# SCH_DA2_fix_2023-07-17.net
KiCad netlist of a schematic drawn in EasyEDA
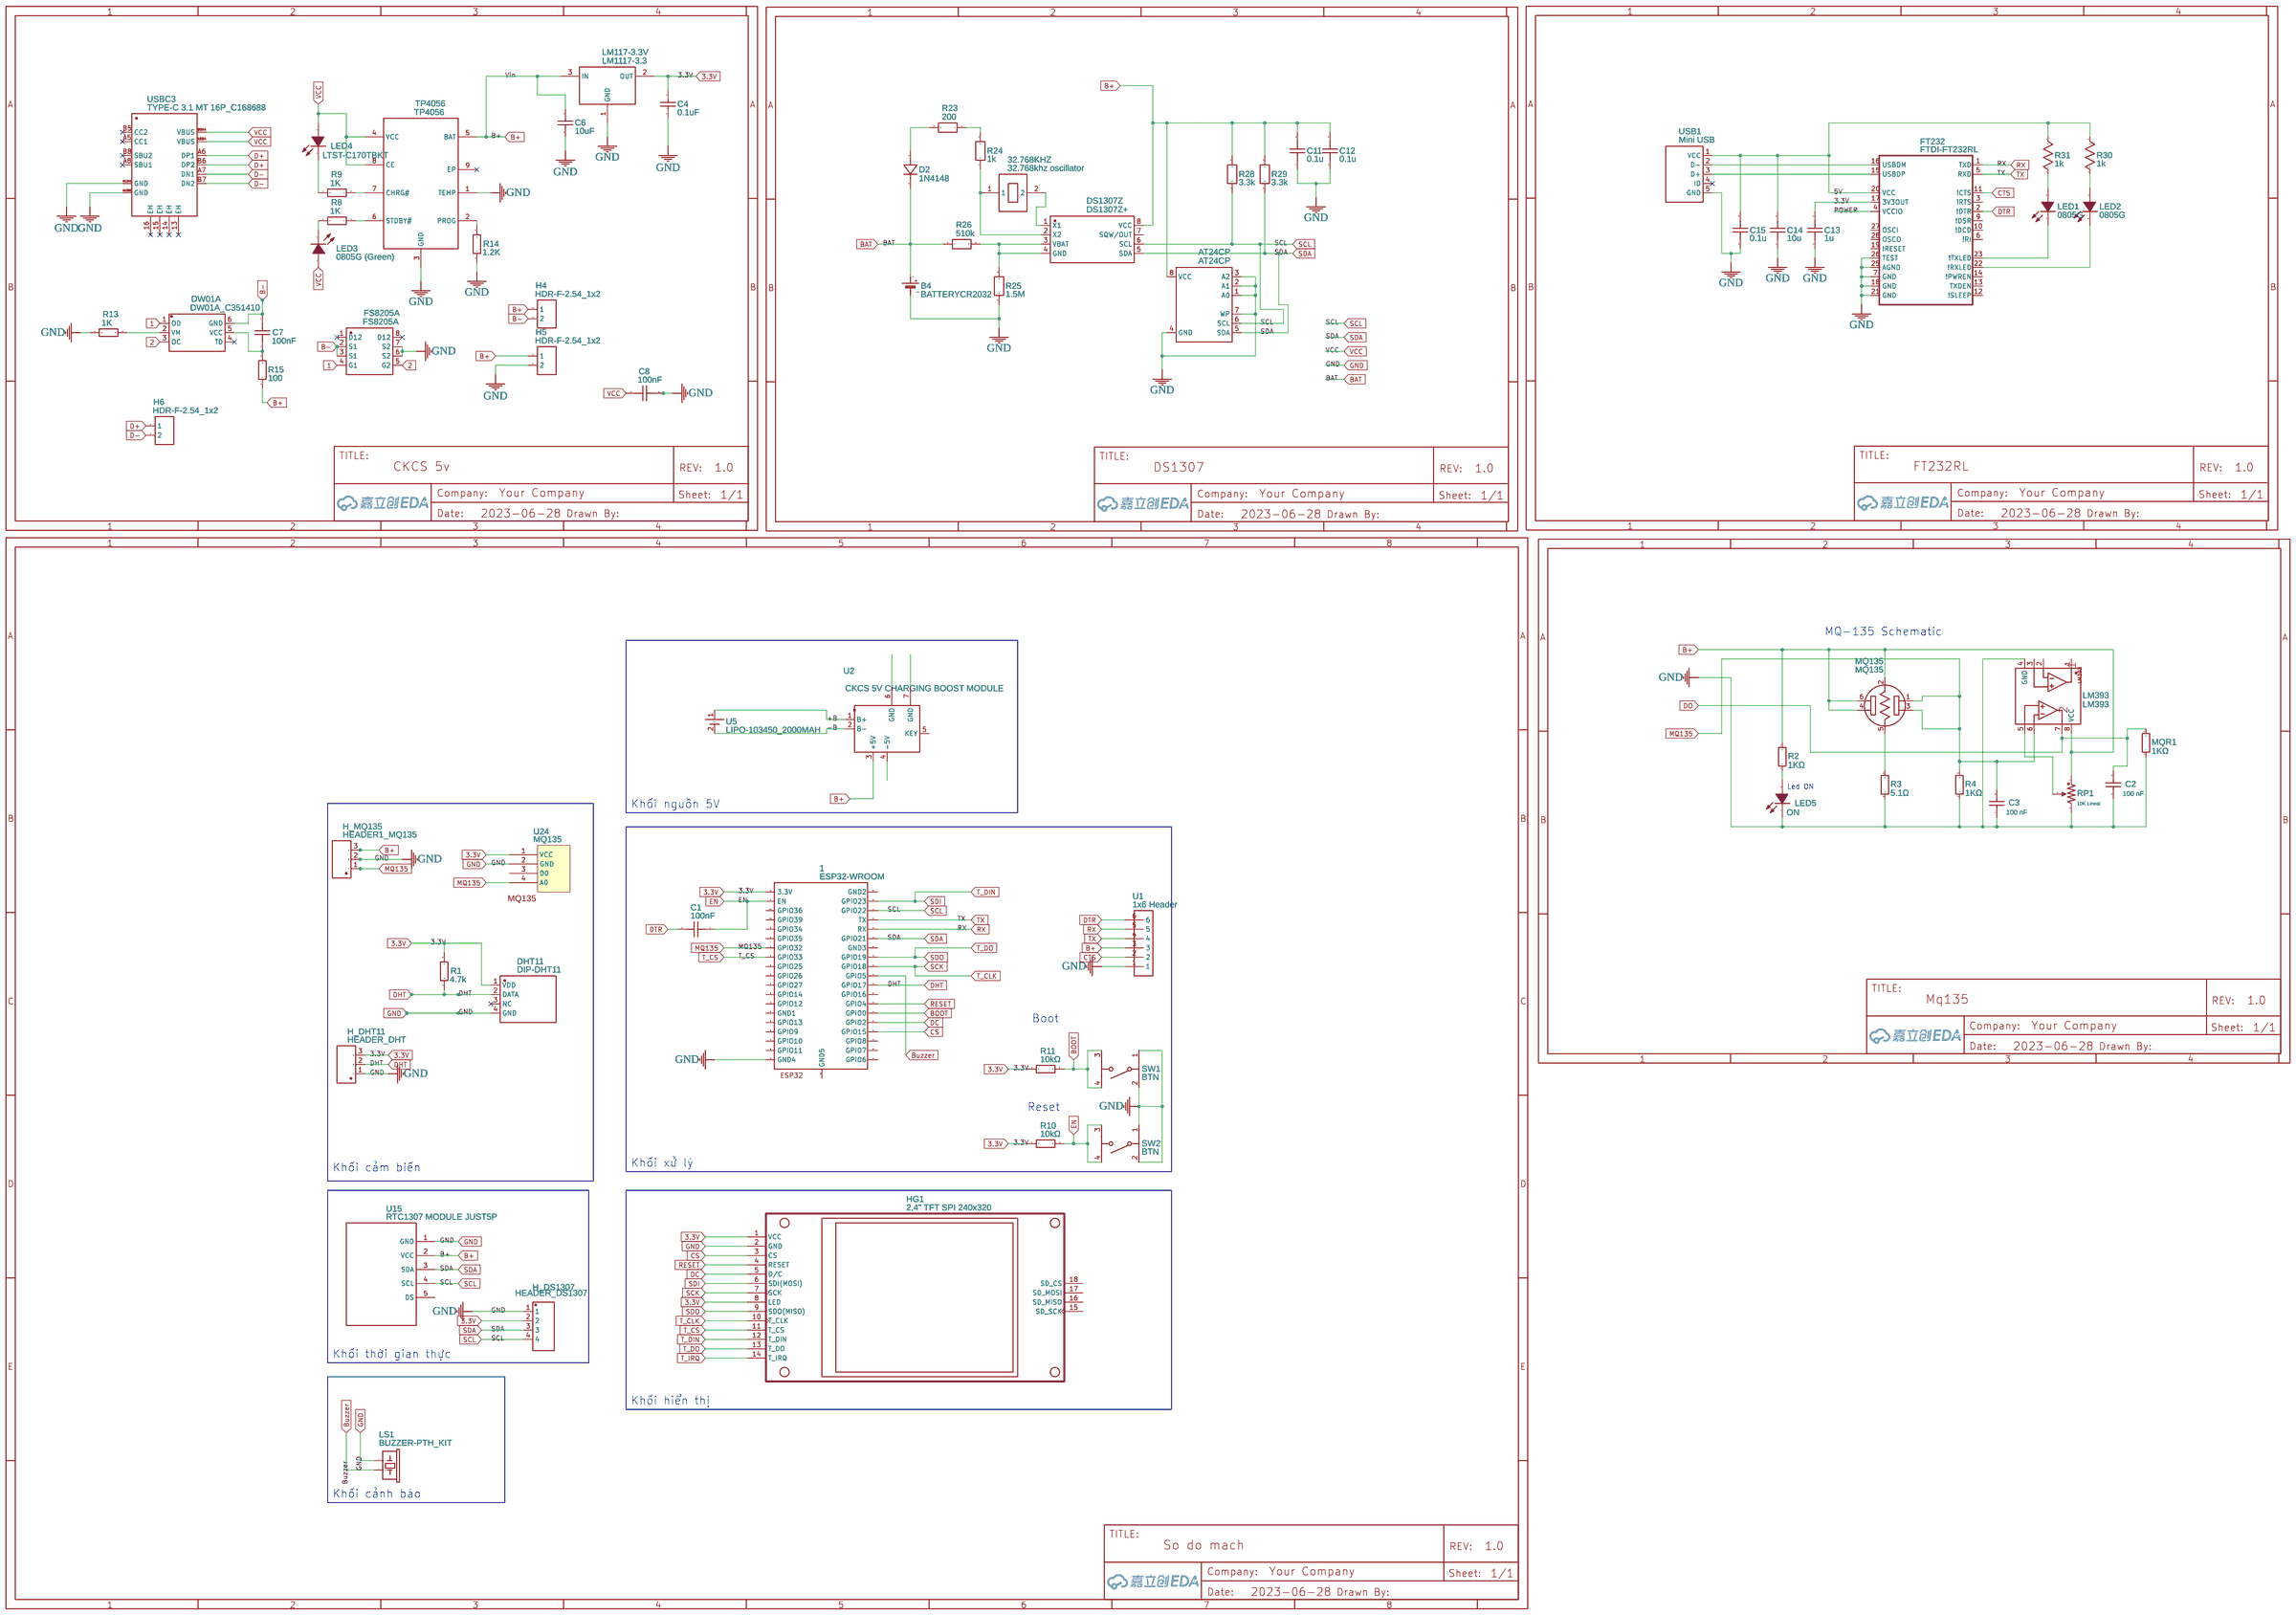
[diagram p0: schematic sheet]

(export (version "E")
  (design (tool "Eeschema 10.0.6"))
  (components
    (comp (ref "1") (value "ESP32-WROOM") (libsource (lib "") (part "ESP32-WROOM")))
    (comp (ref "32.768KHZ") (value "32.768khz oscillator") (libsource (lib "") (part "32.768khz oscillator")))
    (comp (ref "AT24CP") (value "AT24CP") (libsource (lib "") (part "AT24CP")))
    (comp (ref "B4") (value "BATTERYCR2032") (libsource (lib "") (part "BATTERYCR2032")))
    (comp (ref "C1")
      (value "100nF")
      (fields
        (field (name "BOM_Manufacturer Part") "C0805B104M500NT")
        (field (name "BOM_Supplier Part") "C515949")
      )
      (libsource (lib "") (part "C0805B104M500NT"))
    )
    (comp (ref "C2")
      (value "100 nF")
      (fields
        (field (name "BOM_Manufacturer Part") "0.1UF(104) +-20% 63v")
        (field (name "BOM_Supplier Part") "C19355")
      )
      (libsource (lib "") (part "Cap."))
    )
    (comp (ref "C3")
      (value "100 nF")
      (fields
        (field (name "BOM_Manufacturer Part") "0.1UF(104) +-20% 63v")
        (field (name "BOM_Supplier Part") "C19355")
      )
      (libsource (lib "") (part "Cap."))
    )
    (comp (ref "C4")
      (value "0.1uF")
      (fields
        (field (name "BOM_Manufacturer Part") "CC0805KKX5R6BB106")
        (field (name "BOM_Supplier Part") "C89832")
      )
      (libsource (lib "") (part "CC0805KKX5R6BB106"))
    )
    (comp (ref "C6")
      (value "10uF")
      (fields
        (field (name "BOM_Manufacturer Part") "CC0805KKX5R6BB106")
        (field (name "BOM_Supplier Part") "C89832")
      )
      (libsource (lib "") (part "CC0805KKX5R6BB106"))
    )
    (comp (ref "C7")
      (value "100nF")
      (fields
        (field (name "BOM_Manufacturer Part") "C0805B104M500NT")
        (field (name "BOM_Supplier Part") "C515949")
      )
      (libsource (lib "") (part "C0805B104M500NT_1"))
    )
    (comp (ref "C8")
      (value "100nF")
      (fields
        (field (name "BOM_Manufacturer Part") "C0805B104M500NT")
        (field (name "BOM_Supplier Part") "C515949")
      )
      (libsource (lib "") (part "C0805B104M500NT_2"))
    )
    (comp (ref "C11") (value "0.1u") (libsource (lib "") (part "C_0603_US")))
    (comp (ref "C12") (value "0.1u") (libsource (lib "") (part "C_0603_US")))
    (comp (ref "C13")
      (value "1u")
      (fields (field (name "BOM_Manufacturer Part") "?"))
      (libsource (lib "") (part "Cap_1206_US"))
    )
    (comp (ref "C14")
      (value "10u")
      (fields (field (name "BOM_Manufacturer Part") "?"))
      (libsource (lib "") (part "Cap_1206_US"))
    )
    (comp (ref "C15")
      (value "0.1u")
      (fields (field (name "BOM_Manufacturer Part") "?"))
      (libsource (lib "") (part "Cap_1206_US"))
    )
    (comp (ref "D2")
      (value "1N4148")
      (fields
        (field (name "BOM_Manufacturer Part") "1N4148WSG")
        (field (name "BOM_Supplier Part") "C2904852")
      )
      (libsource (lib "") (part "1N4148WSG_C2904852"))
    )
    (comp (ref "DHT11")
      (value "DIP-DHT11")
      (fields (field (name "BOM_Manufacturer Part") "DHT11") (field (name "BOM_Supplier Part") "C117051"))
      (libsource (lib "") (part "DIP-DHT11"))
    )
    (comp (ref "DS1307Z")
      (value "DS1307Z+")
      (fields (field (name "BOM_Supplier Part") "C1520446"))
      (libsource (lib "") (part "DS1307Z+"))
    )
    (comp (ref "DW01A")
      (value "DW01A_C351410")
      (fields (field (name "BOM_Manufacturer Part") "DW01A") (field (name "BOM_Supplier Part") "C351410"))
      (libsource (lib "") (part "DW01A_C351410"))
    )
    (comp (ref "FS8205A")
      (value "FS8205A")
      (fields (field (name "BOM_Supplier Part") "C16052"))
      (libsource (lib "") (part "FS8205A"))
    )
    (comp (ref "FT232")
      (value "FTDI-FT232RL")
      (fields (field (name "BOM_Manufacturer Part") "?"))
      (libsource (lib "") (part "Unknown_2060_-1485"))
    )
    (comp (ref "H4")
      (value "HDR-F-2.54_1x2")
      (fields (field (name "BOM_Supplier Part") "C49661"))
      (libsource (lib "") (part "HDR-F-2.54_1x2"))
    )
    (comp (ref "H5")
      (value "HDR-F-2.54_1x2")
      (fields (field (name "BOM_Supplier Part") "C49661"))
      (libsource (lib "") (part "HDR-F-2.54_1x2"))
    )
    (comp (ref "H6")
      (value "HDR-F-2.54_1x2")
      (fields (field (name "BOM_Supplier Part") "C49661"))
      (libsource (lib "") (part "HDR-F-2.54_1x2"))
    )
    (comp (ref "HG1")
      (value "2,4\" TFT SPI 240x320")
      (fields (field (name "BOM_Manufacturer Part") "2,4\" TFT SPI"))
      (libsource (lib "") (part "2,4&amp;quot; TFT SPI 240x320"))
    )
    (comp (ref "H_DHT11") (value "HEADER_DHT") (libsource (lib "") (part "HEADER1X3_1")))
    (comp (ref "H_DS1307") (value "HEADER_DS1307") (libsource (lib "") (part "HEADER 1X4P COPY COPY")))
    (comp (ref "H_MQ135") (value "HEADER1_MQ135") (libsource (lib "") (part "HEADER1X3")))
    (comp (ref "LED1")
      (value "0805G")
      (fields
        (field (name "BOM_Manufacturer Part") "0805G (Green)")
        (field (name "BOM_Supplier Part") "C2297")
      )
      (libsource (lib "") (part "0805G (Green)"))
    )
    (comp (ref "LED2")
      (value "0805G")
      (fields
        (field (name "BOM_Manufacturer Part") "0805G (Green)")
        (field (name "BOM_Supplier Part") "C2297")
      )
      (libsource (lib "") (part "0805G (Green)"))
    )
    (comp (ref "LED3")
      (value "0805G (Green)")
      (fields (field (name "BOM_Supplier Part") "C2297"))
      (libsource (lib "") (part "0805G (Green)_1"))
    )
    (comp (ref "LED4")
      (value "LTST-C170TBKT")
      (fields (field (name "BOM_Supplier Part") "C98222"))
      (libsource (lib "") (part "LTST-C170TBKT"))
    )
    (comp (ref "LED5")
      (value "ON")
      (fields
        (field (name "BOM_Manufacturer Part") "LTST-C170TBKT")
        (field (name "BOM_Supplier Part") "C98222")
      )
      (libsource (lib "") (part "LTST-C170TBKT"))
    )
    (comp (ref "LM117-3.3V") (value "LM1117-3.3") (libsource (lib "") (part "LM1117-3.3")))
    (comp (ref "LM393")
      (value "LM393")
      (fields
        (field (name "BOM_Manufacturer Part") "LM393DMR2G")
        (field (name "BOM_Supplier Part") "C231851")
      )
      (libsource (lib "") (part "LM393"))
    )
    (comp (ref "LS1") (value "BUZZER-PTH_KIT") (libsource (lib "") (part "BUZZER-PTH_KIT")))
    (comp (ref "MQ135") (value "MQ135") (libsource (lib "") (part "MQ135")))
    (comp (ref "MQR1")
      (value "1KΩ")
      (fields
        (field (name "BOM_Manufacturer Part") "CFR0W4J0472A50")
        (field (name "BOM_Supplier Part") "C61297")
      )
      (libsource (lib "") (part "R_1/4_AXIAL-0.4_1"))
    )
    (comp (ref "R1")
      (value "4.7k")
      (fields
        (field (name "BOM_Manufacturer Part") "RMC06031.2K5%N")
        (field (name "BOM_Supplier Part") "C269681")
      )
      (libsource (lib "") (part "RMC06031.2K5%N"))
    )
    (comp (ref "R2")
      (value "1KΩ")
      (fields
        (field (name "BOM_Manufacturer Part") "CFR0W4J0472A50")
        (field (name "BOM_Supplier Part") "C61297")
      )
      (libsource (lib "") (part "R_1/4_AXIAL-0.4"))
    )
    (comp (ref "R3")
      (value "5.1Ω")
      (fields
        (field (name "BOM_Manufacturer Part") "CFR0W4J0472A50")
        (field (name "BOM_Supplier Part") "C61297")
      )
      (libsource (lib "") (part "R_1/4_AXIAL-0.4"))
    )
    (comp (ref "R4")
      (value "1KΩ")
      (fields
        (field (name "BOM_Manufacturer Part") "CFR0W4J0472A50")
        (field (name "BOM_Supplier Part") "C61297")
      )
      (libsource (lib "") (part "R_1/4_AXIAL-0.4"))
    )
    (comp (ref "R8")
      (value "1K")
      (fields
        (field (name "BOM_Manufacturer Part") "AECR0603F1K00K9")
        (field (name "BOM_Supplier Part") "C328340")
      )
      (libsource (lib "") (part "AECR0603F1K00K9"))
    )
    (comp (ref "R9")
      (value "1K")
      (fields
        (field (name "BOM_Manufacturer Part") "AECR0603F1K00K9")
        (field (name "BOM_Supplier Part") "C328340")
      )
      (libsource (lib "") (part "AECR0603F1K00K9"))
    )
    (comp (ref "R10")
      (value "10kΩ")
      (fields
        (field (name "BOM_Manufacturer Part") "PTFR1206B10K0P9")
        (field (name "BOM_Supplier Part") "C351536")
      )
      (libsource (lib "") (part "PTFR1206B10K0P9"))
    )
    (comp (ref "R11")
      (value "10kΩ")
      (fields
        (field (name "BOM_Manufacturer Part") "PTFR1206B10K0P9")
        (field (name "BOM_Supplier Part") "C351536")
      )
      (libsource (lib "") (part "PTFR1206B10K0P9"))
    )
    (comp (ref "R13")
      (value "1K")
      (fields
        (field (name "BOM_Manufacturer Part") "AECR0603F1K00K9")
        (field (name "BOM_Supplier Part") "C328340")
      )
      (libsource (lib "") (part "AECR0603F1K00K9"))
    )
    (comp (ref "R14")
      (value "1.2K")
      (fields
        (field (name "BOM_Manufacturer Part") "RMC06031.2K5%N")
        (field (name "BOM_Supplier Part") "C269681")
      )
      (libsource (lib "") (part "RMC06031.2K5%N"))
    )
    (comp (ref "R15")
      (value "100")
      (fields
        (field (name "BOM_Manufacturer Part") "AECR0603F100RK9")
        (field (name "BOM_Supplier Part") "C328334")
      )
      (libsource (lib "") (part "AECR0603F100RK9"))
    )
    (comp (ref "R23") (value "200") (libsource (lib "") (part "R_0603_EU_1")))
    (comp (ref "R24") (value "1k") (libsource (lib "") (part "R_0603_EU")))
    (comp (ref "R25") (value "1.5M") (libsource (lib "") (part "R_0603_EU")))
    (comp (ref "R26") (value "510k") (libsource (lib "") (part "R_0603_EU_2")))
    (comp (ref "R28") (value "3.3k") (libsource (lib "") (part "R_0603_EU")))
    (comp (ref "R29") (value "3.3k") (libsource (lib "") (part "R_0603_EU")))
    (comp (ref "R30")
      (value "1k")
      (fields (field (name "BOM_Manufacturer Part") "?"))
      (libsource (lib "") (part "Res_1206(1/4W)_US"))
    )
    (comp (ref "R31")
      (value "1k")
      (fields (field (name "BOM_Manufacturer Part") "?"))
      (libsource (lib "") (part "Res_1206(1/4W)_US"))
    )
    (comp (ref "RP1") (value "10K Lineal") (libsource (lib "") (part "R_3386P_US")))
    (comp (ref "SW1")
      (value "BTN")
      (fields
        (field (name "BOM_Manufacturer Part") "Switch,6*6*6Plastic head,260G, 0.25mm,Straight line")
        (field (name "BOM_Supplier Part") "C71836")
      )
      (libsource (lib "") (part "Button-6x6x6mm"))
    )
    (comp (ref "SW2")
      (value "BTN")
      (fields
        (field (name "BOM_Manufacturer Part") "Switch,6*6*6Plastic head,260G, 0.25mm,Straight line")
        (field (name "BOM_Supplier Part") "C71836")
      )
      (libsource (lib "") (part "Button-6x6x6mm"))
    )
    (comp (ref "TP4056")
      (value "TP4056")
      (fields (field (name "BOM_Supplier Part") "C16581"))
      (libsource (lib "") (part "TP4056"))
    )
    (comp (ref "U1") (value "1x6 Header") (libsource (lib "") (part "1x6 Header")))
    (comp (ref "U2")
      (value "CKCS 5V CHARGING BOOST MODULE")
      (libsource (lib "") (part "CKCS 5V CHARGING BOOST MODULE"))
    )
    (comp (ref "U5") (value "LIPO-103450_2000MAH") (libsource (lib "") (part "LIPO-103450_2000MAH")))
    (comp (ref "U15") (value "RTC1307 MODULE JUST5P") (libsource (lib "") (part "RTC1307 MODULE JUST5P")))
    (comp (ref "U24") (value "MQ135") (libsource (lib "") (part "MQ135_1")))
    (comp (ref "USB1") (value "Mini USB") (libsource (lib "") (part "Mini USB")))
    (comp (ref "USBC3")
      (value "TYPE-C 3.1 MT 16P_C168688")
      (fields (field (name "BOM_Supplier Part") "C168688"))
      (libsource (lib "") (part "TYPE-C 3.1 MT 16P_C168688"))
    )
  )
  (nets
    (net (code "1") (name "/+B") (class "Default")
      (node (ref "U2") (pin "1") (pinfunction "B+_1") (pintype "unspecified"))
      (node (ref "U5") (pin "1") (pinfunction "POS_1") (pintype "unspecified"))
    )
    (net (code "2") (name "/-B") (class "Default")
      (node (ref "U2") (pin "2") (pinfunction "B-_2") (pintype "unspecified"))
      (node (ref "U5") (pin "2") (pinfunction "POS_2") (pintype "unspecified"))
    )
    (net (code "3") (name "/5V") (class "Default")
      (node (ref "C14") (pin "2") (pinfunction "2_2") (pintype "unspecified"))
      (node (ref "C15") (pin "2") (pinfunction "2_2") (pintype "unspecified"))
      (node (ref "FT232") (pin "20") (pinfunction "VCC_20") (pintype "bidirectional"))
      (node (ref "R30") (pin "2") (pinfunction "2_2") (pintype "unspecified"))
      (node (ref "R31") (pin "2") (pinfunction "2_2") (pintype "unspecified"))
      (node (ref "USB1") (pin "1") (pinfunction "VCC_1") (pintype "unspecified"))
    )
    (net (code "4") (name "/POWER") (class "Default")
      (node (ref "FT232") (pin "4") (pinfunction "VCCIO_4") (pintype "bidirectional"))
    )
    (net (code "5") (name "1") (class "Default")
      (node (ref "DW01A") (pin "1") (pinfunction "OD_1") (pintype "unspecified"))
      (node (ref "FS8205A") (pin "4") (pinfunction "G1_4") (pintype "unspecified"))
    )
    (net (code "6") (name "2") (class "Default")
      (node (ref "DW01A") (pin "3") (pinfunction "OC_3") (pintype "unspecified"))
      (node (ref "FS8205A") (pin "5") (pinfunction "G2_5") (pintype "unspecified"))
    )
    (net (code "7") (name "3.3V") (class "Default")
      (node (ref "1") (pin "3V3") (pinfunction "3.3V_3V3") (pintype "bidirectional"))
      (node (ref "C13") (pin "2") (pinfunction "2_2") (pintype "unspecified"))
      (node (ref "C4") (pin "1") (pinfunction "1_1") (pintype "input"))
      (node (ref "DHT11") (pin "1") (pinfunction "VDD_1") (pintype "unspecified"))
      (node (ref "FT232") (pin "17") (pinfunction "3V3OUT_17") (pintype "bidirectional"))
      (node (ref "HG1") (pin "1") (pinfunction "VCC_1") (pintype "passive"))
      (node (ref "HG1") (pin "8") (pinfunction "LED_8") (pintype "passive"))
      (node (ref "H_DHT11") (pin "3") (pinfunction "3_3") (pintype "unspecified"))
      (node (ref "H_DS1307") (pin "2") (pinfunction "2_2") (pintype "unspecified"))
      (node (ref "LM117-3.3V") (pin "2") (pinfunction "OUT_2") (pintype "unspecified"))
      (node (ref "R1") (pin "2") (pinfunction "2_2") (pintype "unspecified"))
      (node (ref "R10") (pin "1") (pinfunction "1_1") (pintype "unspecified"))
      (node (ref "R11") (pin "1") (pinfunction "1_1") (pintype "unspecified"))
      (node (ref "U24") (pin "1") (pinfunction "VCC_1") (pintype "unspecified"))
    )
    (net (code "8") (name "B+") (class "Default")
      (node (ref "AT24CP") (pin "8") (pinfunction "VCC_8") (pintype "passive"))
      (node (ref "C11") (pin "2") (pinfunction "2_2") (pintype "unspecified"))
      (node (ref "C12") (pin "2") (pinfunction "2_2") (pintype "unspecified"))
      (node (ref "C6") (pin "1") (pinfunction "1_1") (pintype "input"))
      (node (ref "DS1307Z") (pin "8") (pinfunction "VCC_8") (pintype "unspecified"))
      (node (ref "H4") (pin "1") (pinfunction "1_1") (pintype "input"))
      (node (ref "H5") (pin "1") (pinfunction "1_1") (pintype "input"))
      (node (ref "H_MQ135") (pin "3") (pinfunction "3_3") (pintype "unspecified"))
      (node (ref "LM117-3.3V") (pin "3") (pinfunction "IN_3") (pintype "unspecified"))
      (node (ref "LM393") (pin "8") (pinfunction "VCC_8") (pintype "unspecified"))
      (node (ref "MQ135") (pin "2") (pinfunction "H_2") (pintype "unspecified"))
      (node (ref "MQ135") (pin "4") (pinfunction "4_4") (pintype "unspecified"))
      (node (ref "MQ135") (pin "6") (pinfunction "6_6") (pintype "unspecified"))
      (node (ref "R15") (pin "1") (pinfunction "1_1") (pintype "unspecified"))
      (node (ref "R2") (pin "2") (pinfunction "2_2") (pintype "input"))
      (node (ref "R28") (pin "2") (pinfunction "2_2") (pintype "unspecified"))
      (node (ref "R29") (pin "2") (pinfunction "2_2") (pintype "unspecified"))
      (node (ref "RP1") (pin "1") (pinfunction "1_1") (pintype "unspecified"))
      (node (ref "TP4056") (pin "5") (pinfunction "BAT_5") (pintype "unspecified"))
      (node (ref "U1") (pin "3") (pinfunction "3_3") (pintype "unspecified"))
      (node (ref "U15") (pin "2") (pinfunction "VCC_2") (pintype "unspecified"))
      (node (ref "U2") (pin "3") (pinfunction "+5V_3") (pintype "unspecified"))
    )
    (net (code "9") (name "B-") (class "Default")
      (node (ref "C7") (pin "2") (pinfunction "2_2") (pintype "unspecified"))
      (node (ref "DW01A") (pin "6") (pinfunction "GND_6") (pintype "unspecified"))
      (node (ref "FS8205A") (pin "2") (pinfunction "S1_2") (pintype "unspecified"))
      (node (ref "FS8205A") (pin "3") (pinfunction "S1_3") (pintype "unspecified"))
      (node (ref "H4") (pin "2") (pinfunction "2_2") (pintype "input"))
    )
    (net (code "10") (name "BAT") (class "Default")
      (node (ref "B4") (pin "+") (pinfunction "+_+") (pintype "bidirectional"))
      (node (ref "D2") (pin "1") (pinfunction "K_1") (pintype "unspecified"))
      (node (ref "R26") (pin "1") (pinfunction "1_1") (pintype "unspecified"))
    )
    (net (code "11") (name "BOOT") (class "Default")
      (node (ref "1") (pin "IO0") (pinfunction "GPIO0_IO0") (pintype "bidirectional"))
      (node (ref "R11") (pin "2") (pinfunction "2_2") (pintype "unspecified"))
      (node (ref "SW1") (pin "3") (pinfunction "3_3") (pintype "unspecified"))
      (node (ref "SW1") (pin "4") (pinfunction "4_4") (pintype "unspecified"))
    )
    (net (code "12") (name "Buzzer") (class "Default")
      (node (ref "1") (pin "IO5") (pinfunction "GPIO5_IO5") (pintype "bidirectional"))
      (node (ref "LS1") (pin "-") (pinfunction "2_-") (pintype "bidirectional"))
    )
    (net (code "13") (name "CS") (class "Default")
      (node (ref "1") (pin "IO15") (pinfunction "GPIO15_IO15") (pintype "bidirectional"))
      (node (ref "HG1") (pin "3") (pinfunction "CS_3") (pintype "input"))
    )
    (net (code "14") (name "CTS") (class "Default")
      (node (ref "FT232") (pin "11") (pinfunction "!CTS_11") (pintype "bidirectional"))
      (node (ref "U1") (pin "2") (pinfunction "2_2") (pintype "unspecified"))
    )
    (net (code "15") (name "D+") (class "Default")
      (node (ref "H6") (pin "1") (pinfunction "1_1") (pintype "input"))
      (node (ref "USBC3") (pin "A6") (pinfunction "DP1_A6") (pintype "unspecified"))
      (node (ref "USBC3") (pin "B6") (pinfunction "DP2_B6") (pintype "unspecified"))
    )
    (net (code "16") (name "D-") (class "Default")
      (node (ref "H6") (pin "2") (pinfunction "2_2") (pintype "input"))
      (node (ref "USBC3") (pin "A7") (pinfunction "DN1_A7") (pintype "unspecified"))
      (node (ref "USBC3") (pin "B7") (pinfunction "DN2_B7") (pintype "unspecified"))
    )
    (net (code "17") (name "DC") (class "Default")
      (node (ref "1") (pin "IO2") (pinfunction "GPIO2_IO2") (pintype "bidirectional"))
      (node (ref "HG1") (pin "5") (pinfunction "D/C_5") (pintype "input"))
    )
    (net (code "18") (name "DHT") (class "Default")
      (node (ref "1") (pin "IO17") (pinfunction "GPIO17_IO17") (pintype "bidirectional"))
      (node (ref "DHT11") (pin "2") (pinfunction "DATA_2") (pintype "unspecified"))
      (node (ref "H_DHT11") (pin "2") (pinfunction "2_2") (pintype "unspecified"))
      (node (ref "R1") (pin "1") (pinfunction "1_1") (pintype "unspecified"))
    )
    (net (code "19") (name "DO") (class "Default")
      (node (ref "C2") (pin "2") (pinfunction "2_2") (pintype "input"))
      (node (ref "LM393") (pin "7") (pinfunction "7_7") (pintype "unspecified"))
      (node (ref "MQR1") (pin "2") (pinfunction "2_2") (pintype "input"))
    )
    (net (code "20") (name "DTR") (class "Default")
      (node (ref "C1") (pin "2") (pinfunction "2_2") (pintype "unspecified"))
      (node (ref "FT232") (pin "2") (pinfunction "!DTR_2") (pintype "bidirectional"))
      (node (ref "U1") (pin "6") (pinfunction "6_6") (pintype "unspecified"))
    )
    (net (code "21") (name "EN") (class "Default")
      (node (ref "1") (pin "EN") (pinfunction "EN_EN") (pintype "bidirectional"))
      (node (ref "C1") (pin "1") (pinfunction "1_1") (pintype "unspecified"))
      (node (ref "R10") (pin "2") (pinfunction "2_2") (pintype "unspecified"))
      (node (ref "SW2") (pin "3") (pinfunction "3_3") (pintype "unspecified"))
      (node (ref "SW2") (pin "4") (pinfunction "4_4") (pintype "unspecified"))
    )
    (net (code "22") (name "GND") (class "Default")
      (node (ref "1") (pin "GND4") (pinfunction "GND4_GND4") (pintype "bidirectional"))
      (node (ref "AT24CP") (pin "1") (pinfunction "A0_1") (pintype "input"))
      (node (ref "AT24CP") (pin "2") (pinfunction "A1_2") (pintype "input"))
      (node (ref "AT24CP") (pin "3") (pinfunction "A2_3") (pintype "input"))
      (node (ref "AT24CP") (pin "4") (pinfunction "GND_4") (pintype "passive"))
      (node (ref "AT24CP") (pin "7") (pinfunction "WP_7") (pintype "input"))
      (node (ref "B4") (pin "-") (pinfunction "-_-") (pintype "bidirectional"))
      (node (ref "C11") (pin "1") (pinfunction "1_1") (pintype "unspecified"))
      (node (ref "C12") (pin "1") (pinfunction "1_1") (pintype "unspecified"))
      (node (ref "C13") (pin "1") (pinfunction "1_1") (pintype "unspecified"))
      (node (ref "C14") (pin "1") (pinfunction "1_1") (pintype "unspecified"))
      (node (ref "C15") (pin "1") (pinfunction "1_1") (pintype "unspecified"))
      (node (ref "C2") (pin "1") (pinfunction "1_1") (pintype "input"))
      (node (ref "C3") (pin "1") (pinfunction "1_1") (pintype "input"))
      (node (ref "C4") (pin "2") (pinfunction "2_2") (pintype "input"))
      (node (ref "C6") (pin "2") (pinfunction "2_2") (pintype "input"))
      (node (ref "C8") (pin "2") (pinfunction "2_2") (pintype "unspecified"))
      (node (ref "DHT11") (pin "4") (pinfunction "GND_4") (pintype "unspecified"))
      (node (ref "FS8205A") (pin "6") (pinfunction "S2_6") (pintype "unspecified"))
      (node (ref "FS8205A") (pin "7") (pinfunction "S2_7") (pintype "unspecified"))
      (node (ref "FT232") (pin "18") (pinfunction "GND_18") (pintype "bidirectional"))
      (node (ref "FT232") (pin "21") (pinfunction "GND_21") (pintype "bidirectional"))
      (node (ref "FT232") (pin "25") (pinfunction "AGND_25") (pintype "bidirectional"))
      (node (ref "FT232") (pin "26") (pinfunction "TEST_26") (pintype "bidirectional"))
      (node (ref "FT232") (pin "7") (pinfunction "GND_7") (pintype "bidirectional"))
      (node (ref "H5") (pin "2") (pinfunction "2_2") (pintype "input"))
      (node (ref "HG1") (pin "2") (pinfunction "GND_2") (pintype "passive"))
      (node (ref "H_DHT11") (pin "1") (pinfunction "1_1") (pintype "unspecified"))
      (node (ref "H_DS1307") (pin "1") (pinfunction "1_1") (pintype "unspecified"))
      (node (ref "H_MQ135") (pin "2") (pinfunction "2_2") (pintype "unspecified"))
      (node (ref "LED5") (pin "1") (pinfunction "K_1") (pintype "unspecified"))
      (node (ref "LM117-3.3V") (pin "1") (pinfunction "GND_1") (pintype "unspecified"))
      (node (ref "LM393") (pin "4") (pinfunction "GND_4") (pintype "unspecified"))
      (node (ref "LS1") (pin "+") (pinfunction "1_+") (pintype "bidirectional"))
      (node (ref "MQR1") (pin "1") (pinfunction "1_1") (pintype "input"))
      (node (ref "R13") (pin "1") (pinfunction "1_1") (pintype "unspecified"))
      (node (ref "R14") (pin "1") (pinfunction "1_1") (pintype "unspecified"))
      (node (ref "R25") (pin "1") (pinfunction "1_1") (pintype "unspecified"))
      (node (ref "R3") (pin "1") (pinfunction "1_1") (pintype "input"))
      (node (ref "R4") (pin "1") (pinfunction "1_1") (pintype "input"))
      (node (ref "RP1") (pin "3") (pinfunction "3_3") (pintype "unspecified"))
      (node (ref "SW1") (pin "1") (pinfunction "1_1") (pintype "unspecified"))
      (node (ref "SW1") (pin "2") (pinfunction "2_2") (pintype "unspecified"))
      (node (ref "SW2") (pin "1") (pinfunction "1_1") (pintype "unspecified"))
      (node (ref "SW2") (pin "2") (pinfunction "2_2") (pintype "unspecified"))
      (node (ref "TP4056") (pin "1") (pinfunction "TEMP_1") (pintype "unspecified"))
      (node (ref "TP4056") (pin "3") (pinfunction "GND_3") (pintype "unspecified"))
      (node (ref "U1") (pin "1") (pinfunction "1_1") (pintype "unspecified"))
      (node (ref "U15") (pin "1") (pinfunction "GND_1") (pintype "unspecified"))
      (node (ref "U24") (pin "2") (pinfunction "GND_2") (pintype "unspecified"))
      (node (ref "USB1") (pin "5") (pinfunction "GND_5") (pintype "unspecified"))
      (node (ref "USBC3") (pin "A12B1") (pinfunction "GND_A12B1") (pintype "unspecified"))
      (node (ref "USBC3") (pin "B12A1") (pinfunction "GND_B12A1") (pintype "unspecified"))
    )
    (net (code "23") (name "MQ135") (class "Default")
      (node (ref "1") (pin "IO32") (pinfunction "GPIO32_IO32") (pintype "bidirectional"))
      (node (ref "C3") (pin "2") (pinfunction "2_2") (pintype "input"))
      (node (ref "H_MQ135") (pin "1") (pinfunction "1_1") (pintype "unspecified"))
      (node (ref "LM393") (pin "6") (pinfunction "6_6") (pintype "unspecified"))
      (node (ref "MQ135") (pin "1") (pinfunction "1_1") (pintype "unspecified"))
      (node (ref "MQ135") (pin "3") (pinfunction "3_3") (pintype "unspecified"))
      (node (ref "R4") (pin "2") (pinfunction "2_2") (pintype "input"))
      (node (ref "U24") (pin "4") (pinfunction "A0_4") (pintype "unspecified"))
    )
    (net (code "24") (name "Net-(D2-A)") (class "Default")
      (node (ref "D2") (pin "2") (pinfunction "A_2") (pintype "unspecified"))
      (node (ref "R23") (pin "2") (pinfunction "2_2") (pintype "unspecified"))
    )
    (net (code "25") (name "Net-(DS1307Z-GND)") (class "Default")
      (node (ref "DS1307Z") (pin "3") (pinfunction "VBAT_3") (pintype "unspecified"))
      (node (ref "DS1307Z") (pin "4") (pinfunction "GND_4") (pintype "unspecified"))
      (node (ref "R25") (pin "2") (pinfunction "2_2") (pintype "unspecified"))
      (node (ref "R26") (pin "2") (pinfunction "2_2") (pintype "unspecified"))
    )
    (net (code "26") (name "Net-(DS1307Z-X1)") (class "Default")
      (node (ref "32.768KHZ") (pin "2") (pinfunction "2_2") (pintype "unspecified"))
      (node (ref "DS1307Z") (pin "1") (pinfunction "X1_1") (pintype "unspecified"))
    )
    (net (code "27") (name "Net-(DS1307Z-X2)") (class "Default")
      (node (ref "32.768KHZ") (pin "1") (pinfunction "1_1") (pintype "unspecified"))
      (node (ref "DS1307Z") (pin "2") (pinfunction "X2_2") (pintype "unspecified"))
      (node (ref "R24") (pin "1") (pinfunction "1_1") (pintype "unspecified"))
    )
    (net (code "28") (name "Net-(DW01A-VCC)") (class "Default")
      (node (ref "C7") (pin "1") (pinfunction "1_1") (pintype "unspecified"))
      (node (ref "DW01A") (pin "5") (pinfunction "VCC_5") (pintype "unspecified"))
      (node (ref "R15") (pin "2") (pinfunction "2_2") (pintype "unspecified"))
    )
    (net (code "29") (name "Net-(DW01A-VM)") (class "Default")
      (node (ref "DW01A") (pin "2") (pinfunction "VM_2") (pintype "unspecified"))
      (node (ref "R13") (pin "2") (pinfunction "2_2") (pintype "unspecified"))
    )
    (net (code "30") (name "Net-(FT232-!RXLED)") (class "Default")
      (node (ref "FT232") (pin "22") (pinfunction "!RXLED_22") (pintype "bidirectional"))
      (node (ref "LED2") (pin "1") (pinfunction "K_1") (pintype "unspecified"))
    )
    (net (code "31") (name "Net-(FT232-!TXLED)") (class "Default")
      (node (ref "FT232") (pin "23") (pinfunction "!TXLED_23") (pintype "bidirectional"))
      (node (ref "LED1") (pin "1") (pinfunction "K_1") (pintype "unspecified"))
    )
    (net (code "32") (name "Net-(FT232-USBDM)") (class "Default")
      (node (ref "FT232") (pin "16") (pinfunction "USBDM_16") (pintype "bidirectional"))
      (node (ref "USB1") (pin "2") (pinfunction "D-_2") (pintype "unspecified"))
    )
    (net (code "33") (name "Net-(FT232-USBDP)") (class "Default")
      (node (ref "FT232") (pin "15") (pinfunction "USBDP_15") (pintype "bidirectional"))
      (node (ref "USB1") (pin "3") (pinfunction "D+_3") (pintype "unspecified"))
    )
    (net (code "34") (name "Net-(LED1-A)") (class "Default")
      (node (ref "LED1") (pin "2") (pinfunction "A_2") (pintype "unspecified"))
      (node (ref "R31") (pin "1") (pinfunction "1_1") (pintype "unspecified"))
    )
    (net (code "35") (name "Net-(LED2-A)") (class "Default")
      (node (ref "LED2") (pin "2") (pinfunction "A_2") (pintype "unspecified"))
      (node (ref "R30") (pin "1") (pinfunction "1_1") (pintype "unspecified"))
    )
    (net (code "36") (name "Net-(LED3-K)") (class "Default")
      (node (ref "LED3") (pin "1") (pinfunction "K_1") (pintype "unspecified"))
      (node (ref "R8") (pin "1") (pinfunction "1_1") (pintype "unspecified"))
    )
    (net (code "37") (name "Net-(LED4-K)") (class "Default")
      (node (ref "LED4") (pin "1") (pinfunction "K_1") (pintype "unspecified"))
      (node (ref "R9") (pin "1") (pinfunction "1_1") (pintype "unspecified"))
    )
    (net (code "38") (name "Net-(LED5-A)") (class "Default")
      (node (ref "LED5") (pin "2") (pinfunction "A_2") (pintype "unspecified"))
      (node (ref "R2") (pin "1") (pinfunction "1_1") (pintype "input"))
    )
    (net (code "39") (name "Net-(LM393-Pad5)") (class "Default")
      (node (ref "LM393") (pin "5") (pinfunction "5_5") (pintype "unspecified"))
      (node (ref "RP1") (pin "2") (pinfunction "2_2") (pintype "unspecified"))
    )
    (net (code "40") (name "Net-(MQ135-H-Pad5)") (class "Default")
      (node (ref "MQ135") (pin "5") (pinfunction "H_5") (pintype "unspecified"))
      (node (ref "R3") (pin "2") (pinfunction "2_2") (pintype "input"))
    )
    (net (code "41") (name "Net-(R23-Pad1)") (class "Default")
      (node (ref "R23") (pin "1") (pinfunction "1_1") (pintype "unspecified"))
      (node (ref "R24") (pin "2") (pinfunction "2_2") (pintype "unspecified"))
    )
    (net (code "42") (name "Net-(TP4056-CHRG#)") (class "Default")
      (node (ref "R9") (pin "2") (pinfunction "2_2") (pintype "unspecified"))
      (node (ref "TP4056") (pin "7") (pinfunction "CHRG#_7") (pintype "unspecified"))
    )
    (net (code "43") (name "Net-(TP4056-PROG)") (class "Default")
      (node (ref "R14") (pin "2") (pinfunction "2_2") (pintype "unspecified"))
      (node (ref "TP4056") (pin "2") (pinfunction "PROG_2") (pintype "unspecified"))
    )
    (net (code "44") (name "Net-(TP4056-STDBY#)") (class "Default")
      (node (ref "R8") (pin "2") (pinfunction "2_2") (pintype "unspecified"))
      (node (ref "TP4056") (pin "6") (pinfunction "STDBY#_6") (pintype "unspecified"))
    )
    (net (code "45") (name "RESET") (class "Default")
      (node (ref "1") (pin "IO4") (pinfunction "GPIO4_IO4") (pintype "bidirectional"))
      (node (ref "HG1") (pin "4") (pinfunction "RESET_4") (pintype "input"))
    )
    (net (code "46") (name "RX") (class "Default")
      (node (ref "1") (pin "RX") (pinfunction "RX_RX") (pintype "bidirectional"))
      (node (ref "FT232") (pin "1") (pinfunction "TXD_1") (pintype "bidirectional"))
      (node (ref "U1") (pin "5") (pinfunction "5_5") (pintype "unspecified"))
    )
    (net (code "47") (name "SCK") (class "Default")
      (node (ref "1") (pin "IO18") (pinfunction "GPIO18_IO18") (pintype "bidirectional"))
      (node (ref "HG1") (pin "10") (pinfunction "T_CLK_10") (pintype "input"))
      (node (ref "HG1") (pin "7") (pinfunction "SCK_7") (pintype "input"))
    )
    (net (code "48") (name "SCL") (class "Default")
      (node (ref "1") (pin "IO22") (pinfunction "GPIO22_IO22") (pintype "bidirectional"))
      (node (ref "AT24CP") (pin "6") (pinfunction "SCL_6") (pintype "unspecified"))
      (node (ref "DS1307Z") (pin "6") (pinfunction "SCL_6") (pintype "unspecified"))
      (node (ref "H_DS1307") (pin "4") (pinfunction "4_4") (pintype "unspecified"))
      (node (ref "R28") (pin "1") (pinfunction "1_1") (pintype "unspecified"))
      (node (ref "U15") (pin "4") (pinfunction "SCL_4") (pintype "unspecified"))
    )
    (net (code "49") (name "SDA") (class "Default")
      (node (ref "1") (pin "IO21") (pinfunction "GPIO21_IO21") (pintype "bidirectional"))
      (node (ref "AT24CP") (pin "5") (pinfunction "SDA_5") (pintype "unspecified"))
      (node (ref "DS1307Z") (pin "5") (pinfunction "SDA_5") (pintype "unspecified"))
      (node (ref "H_DS1307") (pin "3") (pinfunction "3_3") (pintype "unspecified"))
      (node (ref "R29") (pin "1") (pinfunction "1_1") (pintype "unspecified"))
      (node (ref "U15") (pin "3") (pinfunction "SDA_3") (pintype "unspecified"))
    )
    (net (code "50") (name "SDI") (class "Default")
      (node (ref "1") (pin "IO23") (pinfunction "GPIO23_IO23") (pintype "bidirectional"))
      (node (ref "HG1") (pin "12") (pinfunction "T_DIN_12") (pintype "input"))
      (node (ref "HG1") (pin "6") (pinfunction "SDI(MOSI)_6") (pintype "input"))
    )
    (net (code "51") (name "SDO") (class "Default")
      (node (ref "1") (pin "IO19") (pinfunction "GPIO19_IO19") (pintype "bidirectional"))
      (node (ref "HG1") (pin "13") (pinfunction "T_DO_13") (pintype "output"))
      (node (ref "HG1") (pin "9") (pinfunction "SDO(MISO)_9") (pintype "output"))
    )
    (net (code "52") (name "TX") (class "Default")
      (node (ref "1") (pin "TX") (pinfunction "TX_TX") (pintype "bidirectional"))
      (node (ref "FT232") (pin "5") (pinfunction "RXD_5") (pintype "bidirectional"))
      (node (ref "U1") (pin "4") (pinfunction "4_4") (pintype "unspecified"))
    )
    (net (code "53") (name "T_CS") (class "Default")
      (node (ref "1") (pin "IO33") (pinfunction "GPIO33_IO33") (pintype "bidirectional"))
      (node (ref "HG1") (pin "11") (pinfunction "T_CS_11") (pintype "input"))
    )
    (net (code "54") (name "T_IRQ") (class "Default")
      (node (ref "HG1") (pin "14") (pinfunction "T_IRQ_14") (pintype "output"))
    )
    (net (code "55") (name "VCC") (class "Default")
      (node (ref "C8") (pin "1") (pinfunction "1_1") (pintype "unspecified"))
      (node (ref "LED3") (pin "2") (pinfunction "A_2") (pintype "unspecified"))
      (node (ref "LED4") (pin "2") (pinfunction "A_2") (pintype "unspecified"))
      (node (ref "TP4056") (pin "4") (pinfunction "VCC_4") (pintype "unspecified"))
      (node (ref "TP4056") (pin "8") (pinfunction "CE_8") (pintype "unspecified"))
      (node (ref "USBC3") (pin "A9B4") (pinfunction "VBUS_A9B4") (pintype "unspecified"))
      (node (ref "USBC3") (pin "B9A4") (pinfunction "VBUS_B9A4") (pintype "unspecified"))
    )
    (net (code "56") (name "unconnected-(1-GPIO6-PadCLK)") (class "Default")
      (node (ref "1") (pin "CLK") (pinfunction "GPIO6_CLK") (pintype "bidirectional"))
    )
    (net (code "57") (name "unconnected-(1-GPIO7-PadSD0)") (class "Default")
      (node (ref "1") (pin "SD0") (pinfunction "GPIO7_SD0") (pintype "bidirectional"))
    )
    (net (code "58") (name "unconnected-(1-GPIO8-PadSD1)") (class "Default")
      (node (ref "1") (pin "SD1") (pinfunction "GPIO8_SD1") (pintype "bidirectional"))
    )
    (net (code "59") (name "unconnected-(1-GPIO9-PadSD2)") (class "Default")
      (node (ref "1") (pin "SD2") (pinfunction "GPIO9_SD2") (pintype "bidirectional"))
    )
    (net (code "60") (name "unconnected-(1-GPIO10-PadSD3)") (class "Default")
      (node (ref "1") (pin "SD3") (pinfunction "GPIO10_SD3") (pintype "bidirectional"))
    )
    (net (code "61") (name "unconnected-(1-GPIO11-PadCMD)") (class "Default")
      (node (ref "1") (pin "CMD") (pinfunction "GPIO11_CMD") (pintype "bidirectional"))
    )
    (net (code "62") (name "unconnected-(1-GPIO12-PadIO12)") (class "Default")
      (node (ref "1") (pin "IO12") (pinfunction "GPIO12_IO12") (pintype "bidirectional"))
    )
    (net (code "63") (name "unconnected-(1-GPIO13-PadIO13)") (class "Default")
      (node (ref "1") (pin "IO13") (pinfunction "GPIO13_IO13") (pintype "bidirectional"))
    )
    (net (code "64") (name "unconnected-(1-GPIO14-PadIO14)") (class "Default")
      (node (ref "1") (pin "IO14") (pinfunction "GPIO14_IO14") (pintype "bidirectional"))
    )
    (net (code "65") (name "unconnected-(1-GPIO16-PadIO16)") (class "Default")
      (node (ref "1") (pin "IO16") (pinfunction "GPIO16_IO16") (pintype "bidirectional"))
    )
    (net (code "66") (name "unconnected-(1-GPIO25-PadIO25)") (class "Default")
      (node (ref "1") (pin "IO25") (pinfunction "GPIO25_IO25") (pintype "bidirectional"))
    )
    (net (code "67") (name "unconnected-(1-GPIO26-PadIO26)") (class "Default")
      (node (ref "1") (pin "IO26") (pinfunction "GPIO26_IO26") (pintype "bidirectional"))
    )
    (net (code "68") (name "unconnected-(1-GPIO27-PadIO27)") (class "Default")
      (node (ref "1") (pin "IO27") (pinfunction "GPIO27_IO27") (pintype "bidirectional"))
    )
    (net (code "69") (name "unconnected-(1-GPIO34-PadIO34)") (class "Default")
      (node (ref "1") (pin "IO34") (pinfunction "GPIO34_IO34") (pintype "bidirectional"))
    )
    (net (code "70") (name "unconnected-(1-GPIO35-PadIO35)") (class "Default")
      (node (ref "1") (pin "IO35") (pinfunction "GPIO35_IO35") (pintype "bidirectional"))
    )
    (net (code "71") (name "unconnected-(1-GPIO36-PadSENSOR_VP)") (class "Default")
      (node (ref "1") (pin "SENSOR_VP") (pinfunction "GPIO36_SENSOR_VP") (pintype "bidirectional"))
    )
    (net (code "72") (name "unconnected-(1-GPIO39-PadSENSOR_VN)") (class "Default")
      (node (ref "1") (pin "SENSOR_VN") (pinfunction "GPIO39_SENSOR_VN") (pintype "bidirectional"))
    )
    (net (code "73") (name "unconnected-(1-PadGND1)") (class "Default")
      (node (ref "1") (pin "GND1") (pinfunction "GND1_GND1") (pintype "bidirectional"))
    )
    (net (code "74") (name "unconnected-(1-PadGND2)") (class "Default")
      (node (ref "1") (pin "GND2") (pinfunction "GND2_GND2") (pintype "bidirectional"))
    )
    (net (code "75") (name "unconnected-(1-PadGND3)") (class "Default")
      (node (ref "1") (pin "GND3") (pinfunction "GND3_GND3") (pintype "bidirectional"))
    )
    (net (code "76") (name "unconnected-(1-PadGND5)") (class "Default")
      (node (ref "1") (pin "GND5") (pinfunction "GND5_GND5") (pintype "bidirectional"))
    )
    (net (code "77") (name "unconnected-(DHT11-NC-Pad3)") (class "Default")
      (node (ref "DHT11") (pin "3") (pinfunction "NC_3") (pintype "unspecified+no_connect"))
    )
    (net (code "78") (name "unconnected-(DS1307Z-SQW{slash}OUT-Pad7)") (class "Default")
      (node (ref "DS1307Z") (pin "7") (pinfunction "SQW/OUT_7") (pintype "unspecified"))
    )
    (net (code "79") (name "unconnected-(DW01A-TD-Pad4)") (class "Default")
      (node (ref "DW01A") (pin "4") (pinfunction "TD_4") (pintype "unspecified+no_connect"))
    )
    (net (code "80") (name "unconnected-(FS8205A-D12-Pad1)") (class "Default")
      (node (ref "FS8205A") (pin "1") (pinfunction "D12_1") (pintype "unspecified+no_connect"))
    )
    (net (code "81") (name "unconnected-(FS8205A-D12-Pad8)") (class "Default")
      (node (ref "FS8205A") (pin "8") (pinfunction "D12_8") (pintype "unspecified+no_connect"))
    )
    (net (code "82") (name "unconnected-(FT232-!DCD-Pad10)") (class "Default")
      (node (ref "FT232") (pin "10") (pinfunction "!DCD_10") (pintype "bidirectional"))
    )
    (net (code "83") (name "unconnected-(FT232-!DSR-Pad9)") (class "Default")
      (node (ref "FT232") (pin "9") (pinfunction "!DSR_9") (pintype "bidirectional"))
    )
    (net (code "84") (name "unconnected-(FT232-!PWREN-Pad14)") (class "Default")
      (node (ref "FT232") (pin "14") (pinfunction "!PWREN_14") (pintype "bidirectional"))
    )
    (net (code "85") (name "unconnected-(FT232-!RESET-Pad19)") (class "Default")
      (node (ref "FT232") (pin "19") (pinfunction "!RESET_19") (pintype "bidirectional"))
    )
    (net (code "86") (name "unconnected-(FT232-!RI-Pad6)") (class "Default")
      (node (ref "FT232") (pin "6") (pinfunction "!RI_6") (pintype "bidirectional"))
    )
    (net (code "87") (name "unconnected-(FT232-!RTS-Pad3)") (class "Default")
      (node (ref "FT232") (pin "3") (pinfunction "!RTS_3") (pintype "bidirectional"))
    )
    (net (code "88") (name "unconnected-(FT232-!SLEEP-Pad12)") (class "Default")
      (node (ref "FT232") (pin "12") (pinfunction "!SLEEP_12") (pintype "bidirectional"))
    )
    (net (code "89") (name "unconnected-(FT232-OSCI-Pad27)") (class "Default")
      (node (ref "FT232") (pin "27") (pinfunction "OSCI_27") (pintype "bidirectional"))
    )
    (net (code "90") (name "unconnected-(FT232-OSCO-Pad28)") (class "Default")
      (node (ref "FT232") (pin "28") (pinfunction "OSCO_28") (pintype "bidirectional"))
    )
    (net (code "91") (name "unconnected-(FT232-TXDEN-Pad13)") (class "Default")
      (node (ref "FT232") (pin "13") (pinfunction "TXDEN_13") (pintype "bidirectional"))
    )
    (net (code "92") (name "unconnected-(HG1-SD_CS-Pad18)") (class "Default")
      (node (ref "HG1") (pin "18") (pinfunction "SD_CS_18") (pintype "input"))
    )
    (net (code "93") (name "unconnected-(HG1-SD_MISO-Pad16)") (class "Default")
      (node (ref "HG1") (pin "16") (pinfunction "SD_MISO_16") (pintype "output"))
    )
    (net (code "94") (name "unconnected-(HG1-SD_MOSI-Pad17)") (class "Default")
      (node (ref "HG1") (pin "17") (pinfunction "SD_MOSI_17") (pintype "input"))
    )
    (net (code "95") (name "unconnected-(HG1-SD_SCK-Pad15)") (class "Default")
      (node (ref "HG1") (pin "15") (pinfunction "SD_SCK_15") (pintype "input"))
    )
    (net (code "96") (name "unconnected-(LM393-IN1--Pad2)") (class "Default")
      (node (ref "LM393") (pin "2") (pinfunction "IN1-_2") (pintype "unspecified"))
    )
    (net (code "97") (name "unconnected-(LM393-OUT_1-Pad1)") (class "Default")
      (node (ref "LM393") (pin "1") (pinfunction "OUT_1_1") (pintype "unspecified"))
    )
    (net (code "98") (name "unconnected-(LM393-Pad3)") (class "Default")
      (node (ref "LM393") (pin "3") (pinfunction "3_3") (pintype "unspecified"))
    )
    (net (code "99") (name "unconnected-(TP4056-EP-Pad9)") (class "Default")
      (node (ref "TP4056") (pin "9") (pinfunction "EP_9") (pintype "unspecified+no_connect"))
    )
    (net (code "100") (name "unconnected-(U2--5V-Pad4)") (class "Default")
      (node (ref "U2") (pin "4") (pinfunction "-5V_4") (pintype "unspecified"))
    )
    (net (code "101") (name "unconnected-(U2-GND-Pad6)") (class "Default")
      (node (ref "U2") (pin "6") (pinfunction "GND_6") (pintype "unspecified"))
    )
    (net (code "102") (name "unconnected-(U2-GND-Pad7)") (class "Default")
      (node (ref "U2") (pin "7") (pinfunction "GND_7") (pintype "unspecified"))
    )
    (net (code "103") (name "unconnected-(U2-KEY-Pad5)") (class "Default")
      (node (ref "U2") (pin "5") (pinfunction "KEY_5") (pintype "unspecified"))
    )
    (net (code "104") (name "unconnected-(U15-DS-Pad5)") (class "Default")
      (node (ref "U15") (pin "5") (pinfunction "DS_5") (pintype "unspecified"))
    )
    (net (code "105") (name "unconnected-(U24-D0-Pad3)") (class "Default")
      (node (ref "U24") (pin "3") (pinfunction "D0_3") (pintype "unspecified"))
    )
    (net (code "106") (name "unconnected-(USB1-ID-Pad4)") (class "Default")
      (node (ref "USB1") (pin "4") (pinfunction "ID_4") (pintype "unspecified+no_connect"))
    )
    (net (code "107") (name "unconnected-(USBC3-CC1-PadA5)") (class "Default")
      (node (ref "USBC3") (pin "A5") (pinfunction "CC1_A5") (pintype "unspecified+no_connect"))
    )
    (net (code "108") (name "unconnected-(USBC3-CC2-PadB5)") (class "Default")
      (node (ref "USBC3") (pin "B5") (pinfunction "CC2_B5") (pintype "unspecified+no_connect"))
    )
    (net (code "109") (name "unconnected-(USBC3-EH-Pad13)") (class "Default")
      (node (ref "USBC3") (pin "13") (pinfunction "EH_13") (pintype "unspecified+no_connect"))
    )
    (net (code "110") (name "unconnected-(USBC3-EH-Pad14)") (class "Default")
      (node (ref "USBC3") (pin "14") (pinfunction "EH_14") (pintype "unspecified+no_connect"))
    )
    (net (code "111") (name "unconnected-(USBC3-EH-Pad15)") (class "Default")
      (node (ref "USBC3") (pin "15") (pinfunction "EH_15") (pintype "unspecified+no_connect"))
    )
    (net (code "112") (name "unconnected-(USBC3-EH-Pad16)") (class "Default")
      (node (ref "USBC3") (pin "16") (pinfunction "EH_16") (pintype "unspecified+no_connect"))
    )
    (net (code "113") (name "unconnected-(USBC3-SBU1-PadA8)") (class "Default")
      (node (ref "USBC3") (pin "A8") (pinfunction "SBU1_A8") (pintype "unspecified+no_connect"))
    )
    (net (code "114") (name "unconnected-(USBC3-SBU2-PadB8)") (class "Default")
      (node (ref "USBC3") (pin "B8") (pinfunction "SBU2_B8") (pintype "unspecified+no_connect"))
    )
  )
)
